# 780-00055_rev2_Pg2_SCH_NRES_Temp_Meas_8-.net
KiCad netlist of a schematic drawn in Altium Designer
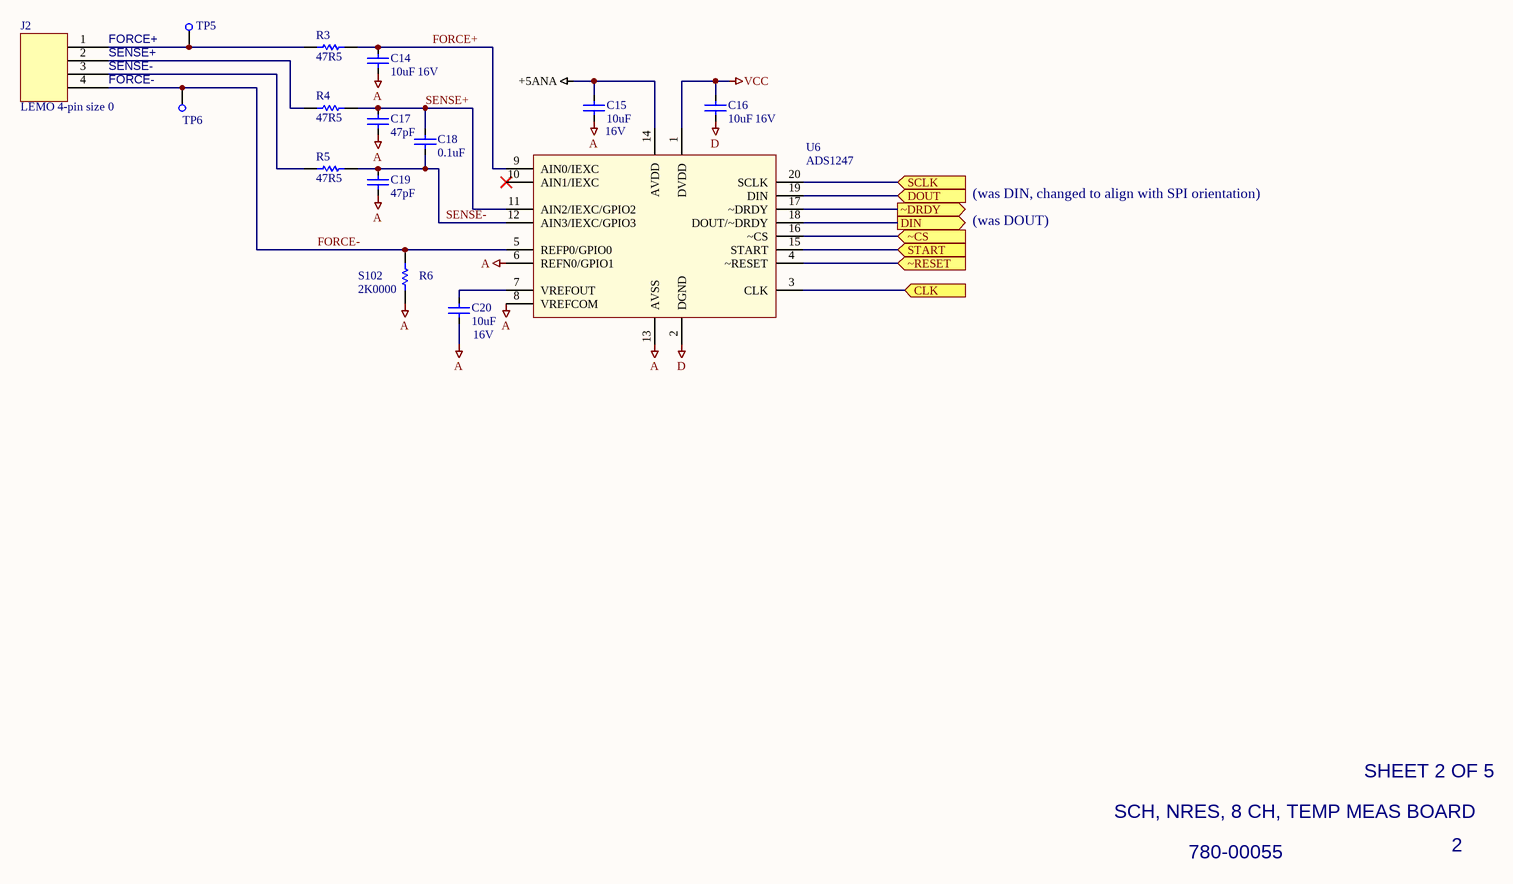
[diagram p0: 780-00055, rev2, Pg2, SCH, NRES Temp Meas, 8-Chan RTD .SchDoc]

(export (version "E")
  (design (tool "Eeschema 10.0.6"))
  (components
    (comp (ref "C14")
      (value "16V")
      (footprint "SMD_0805")
      (description "Capacitor")
      (fields (field (name "ALTIUM_VALUE") "10uF"))
      (libsource (lib "Richs Schematic Components") (part "Cap SMD"))
    )
    (comp (ref "C15")
      (value "16V")
      (footprint "SMD_0805")
      (description "Capacitor")
      (fields (field (name "ALTIUM_VALUE") "10uF"))
      (libsource (lib "Richs Schematic Components") (part "Cap SMD"))
    )
    (comp (ref "C16")
      (value "16V")
      (footprint "SMD_0805")
      (description "Capacitor")
      (fields (field (name "ALTIUM_VALUE") "10uF"))
      (libsource (lib "Richs Schematic Components") (part "Cap SMD"))
    )
    (comp (ref "C17")
      (value "47pF")
      (footprint "SMD_0805")
      (description "Capacitor")
      (fields (field (name "Comment") "Cap SMD"))
      (libsource (lib "Richs Schematic Components") (part "Cap SMD"))
    )
    (comp (ref "C18")
      (value "0.1uF")
      (footprint "SMD_0805")
      (description "Capacitor")
      (fields (field (name "Comment") "Cap SMD"))
      (libsource (lib "Richs Schematic Components") (part "Cap SMD"))
    )
    (comp (ref "C19")
      (value "47pF")
      (footprint "SMD_0805")
      (description "Capacitor")
      (fields (field (name "Comment") "Cap SMD"))
      (libsource (lib "Richs Schematic Components") (part "Cap SMD"))
    )
    (comp (ref "C20")
      (value "16V")
      (footprint "SMD_0805")
      (description "Capacitor")
      (fields (field (name "ALTIUM_VALUE") "10uF"))
      (libsource (lib "Richs Schematic Components") (part "Cap SMD"))
    )
    (comp (ref "J2")
      (value "LEMO 4-pin size 0")
      (footprint "LEMO Size 0, 4-pin PCB")
      (libsource (lib "Richs Schematic Components") (part "LEMO Size 0, 4 pin, PCB"))
    )
    (comp (ref "R3")
      (value "47R5")
      (footprint "SMD_0805")
      (description "Resistor 0805")
      (fields (field (name "MANUFACTURER") "Vishay/Dale") (field (name "Comment") "Res 0805"))
      (libsource (lib "Richs Schematic Components") (part "Res SMD"))
    )
    (comp (ref "R4")
      (value "47R5")
      (footprint "SMD_0805")
      (description "Resistor 0805")
      (fields (field (name "MANUFACTURER") "Vishay/Dale") (field (name "Comment") "Res 0805"))
      (libsource (lib "Richs Schematic Components") (part "Res SMD"))
    )
    (comp (ref "R5")
      (value "47R5")
      (footprint "SMD_0805")
      (description "Resistor 0805")
      (fields (field (name "MANUFACTURER") "Vishay/Dale") (field (name "Comment") "Res 0805"))
      (libsource (lib "Richs Schematic Components") (part "Res SMD"))
    )
    (comp (ref "R6")
      (value "S102")
      (footprint "Vishay S102 series")
      (description "Vishay Foil Resistor")
      (fields (field (name "ALTIUM_VALUE") "2K0000"))
      (libsource (lib "Richs Schematic Components") (part "RES TH Radial"))
    )
    (comp (ref "TP5")
      (value "Test point")
      (footprint "Protel 99SE BANKS PCB:PAD_80D_052H")
      (description "Test Point")
      (fields (field (name "MANUFACTURER") "Keystone"))
      (libsource (lib "Richs Schematic Components") (part "Test point"))
    )
    (comp (ref "TP6")
      (value "Test point")
      (footprint "Protel 99SE BANKS PCB:PAD_80D_052H")
      (description "Test Point")
      (fields (field (name "MANUFACTURER") "Keystone"))
      (libsource (lib "Richs Schematic Components") (part "Test point"))
    )
    (comp (ref "U6")
      (value "ADS1247")
      (footprint "TSSOP20")
      (description "24bit ADC for Temp Sensors")
      (fields (field (name "MANUFACTURER") "TI"))
      (libsource (lib "Richs Schematic Components") (part "ADS1247"))
    )
  )
  (nets
    (net (code "1") (name "+5ANA") (class "Default")
      (node (ref "C15") (pin "2") (pinfunction "2_2") (pintype "passive"))
      (node (ref "U6") (pin "14") (pinfunction "AVDD_14") (pintype "passive"))
    )
    (net (code "2") (name "/CLK") (class "Default")
      (node (ref "U6") (pin "3") (pinfunction "CLK_3") (pintype "passive"))
    )
    (net (code "3") (name "/DIN") (class "Default")
      (node (ref "U6") (pin "18") (pinfunction "DOUT/~DRDY_18") (pintype "passive"))
    )
    (net (code "4") (name "/DOUT") (class "Default")
      (node (ref "U6") (pin "19") (pinfunction "DIN_19") (pintype "passive"))
    )
    (net (code "5") (name "/FORCE+") (class "Default")
      (node (ref "C14") (pin "2") (pinfunction "2_2") (pintype "passive"))
      (node (ref "R3") (pin "2") (pinfunction "2_2") (pintype "passive"))
      (node (ref "U6") (pin "9") (pinfunction "AIN0/IEXC_9") (pintype "passive"))
    )
    (net (code "6") (name "/FORCE-") (class "Default")
      (node (ref "J2") (pin "4") (pinfunction "S32_4") (pintype "passive"))
      (node (ref "R6") (pin "2") (pinfunction "2_2") (pintype "passive"))
      (node (ref "TP6") (pin "1") (pinfunction "TP_1") (pintype "passive"))
      (node (ref "U6") (pin "5") (pinfunction "REFP0/GPIO0_5") (pintype "passive"))
    )
    (net (code "7") (name "/SCLK") (class "Default")
      (node (ref "U6") (pin "20") (pinfunction "SCLK_20") (pintype "passive"))
    )
    (net (code "8") (name "/SENSE+") (class "Default")
      (node (ref "C17") (pin "2") (pinfunction "2_2") (pintype "passive"))
      (node (ref "C18") (pin "2") (pinfunction "2_2") (pintype "passive"))
      (node (ref "R4") (pin "2") (pinfunction "2_2") (pintype "passive"))
      (node (ref "U6") (pin "11") (pinfunction "AIN2/IEXC/GPIO2_11") (pintype "passive"))
    )
    (net (code "9") (name "/SENSE-") (class "Default")
      (node (ref "C18") (pin "1") (pinfunction "1_1") (pintype "passive"))
      (node (ref "C19") (pin "2") (pinfunction "2_2") (pintype "passive"))
      (node (ref "R5") (pin "2") (pinfunction "2_2") (pintype "passive"))
      (node (ref "U6") (pin "12") (pinfunction "AIN3/IEXC/GPIO3_12") (pintype "passive"))
    )
    (net (code "10") (name "/START") (class "Default")
      (node (ref "U6") (pin "15") (pinfunction "START_15") (pintype "passive"))
    )
    (net (code "11") (name "/~CS") (class "Default")
      (node (ref "U6") (pin "16") (pinfunction "~CS_16") (pintype "passive"))
    )
    (net (code "12") (name "/~DRDY") (class "Default")
      (node (ref "U6") (pin "17") (pinfunction "~DRDY_17") (pintype "passive"))
    )
    (net (code "13") (name "/~RESET") (class "Default")
      (node (ref "U6") (pin "4") (pinfunction "~RESET_4") (pintype "passive"))
    )
    (net (code "14") (name "A") (class "Default")
      (node (ref "C14") (pin "1") (pinfunction "1_1") (pintype "passive"))
      (node (ref "C15") (pin "1") (pinfunction "1_1") (pintype "passive"))
      (node (ref "C17") (pin "1") (pinfunction "1_1") (pintype "passive"))
      (node (ref "C19") (pin "1") (pinfunction "1_1") (pintype "passive"))
      (node (ref "C20") (pin "1") (pinfunction "1_1") (pintype "passive"))
      (node (ref "R6") (pin "1") (pinfunction "1_1") (pintype "passive"))
      (node (ref "U6") (pin "13") (pinfunction "AVSS_13") (pintype "passive"))
      (node (ref "U6") (pin "6") (pinfunction "REFN0/GPIO1_6") (pintype "passive"))
      (node (ref "U6") (pin "8") (pinfunction "VREFCOM_8") (pintype "passive"))
    )
    (net (code "15") (name "D") (class "Default")
      (node (ref "C16") (pin "1") (pinfunction "1_1") (pintype "passive"))
      (node (ref "U6") (pin "2") (pinfunction "DGND_2") (pintype "passive"))
    )
    (net (code "16") (name "Net-(J2-S29)") (class "Default")
      (node (ref "J2") (pin "1") (pinfunction "S29_1") (pintype "passive"))
      (node (ref "R3") (pin "1") (pinfunction "1_1") (pintype "passive"))
      (node (ref "TP5") (pin "1") (pinfunction "TP_1") (pintype "passive"))
    )
    (net (code "17") (name "Net-(J2-S30)") (class "Default")
      (node (ref "J2") (pin "2") (pinfunction "S30_2") (pintype "passive"))
      (node (ref "R4") (pin "1") (pinfunction "1_1") (pintype "passive"))
    )
    (net (code "18") (name "Net-(J2-S31)") (class "Default")
      (node (ref "J2") (pin "3") (pinfunction "S31_3") (pintype "passive"))
      (node (ref "R5") (pin "1") (pinfunction "1_1") (pintype "passive"))
    )
    (net (code "19") (name "Net-(U6-VREFOUT)") (class "Default")
      (node (ref "C20") (pin "2") (pinfunction "2_2") (pintype "passive"))
      (node (ref "U6") (pin "7") (pinfunction "VREFOUT_7") (pintype "passive"))
    )
    (net (code "20") (name "VCC") (class "Default")
      (node (ref "C16") (pin "2") (pinfunction "2_2") (pintype "passive"))
      (node (ref "U6") (pin "1") (pinfunction "DVDD_1") (pintype "passive"))
    )
    (net (code "21") (name "unconnected-(U6-AIN1{slash}IEXC-Pad10)") (class "Default")
      (node (ref "U6") (pin "10") (pinfunction "AIN1/IEXC_10") (pintype "passive+no_connect"))
    )
  )
)
